# Sheet1.net
KiCad netlist of a schematic drawn in Altium Designer
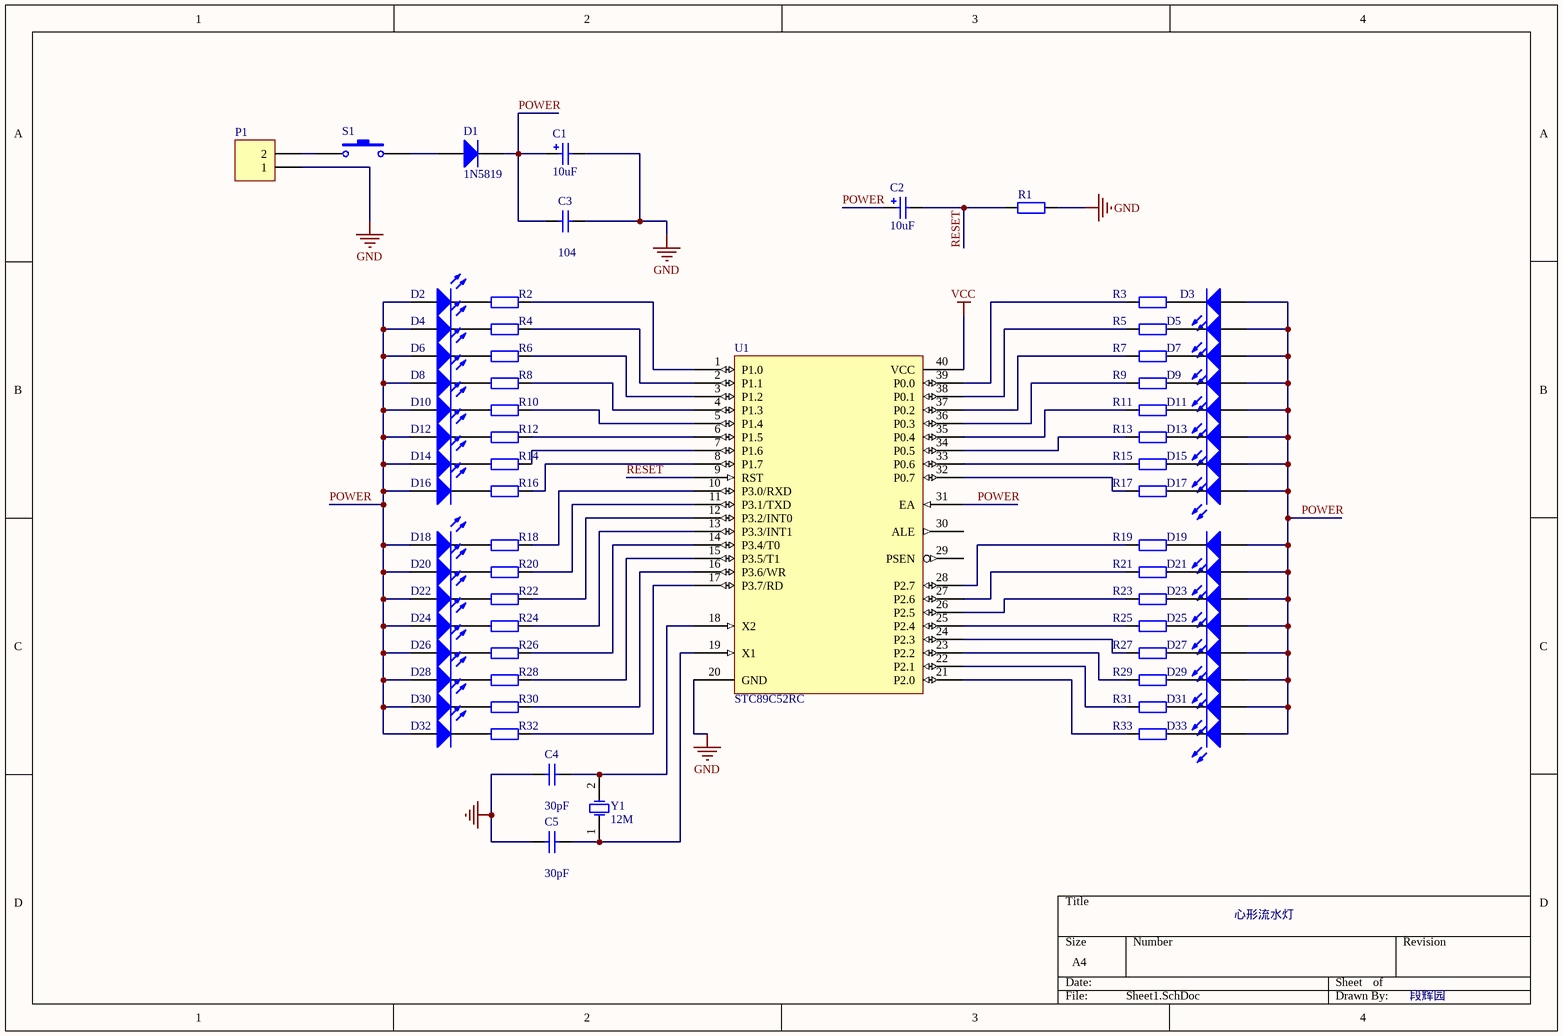
[diagram p0: Sheet1.SchDoc]

(export (version "E")
  (design (tool "Eeschema 10.0.6"))
  (components
    (comp (ref "C1")
      (value "10uF")
      (footprint "RB7.6-15")
      (description "Polarized Capacitor (Radial)")
      (fields (field (name "Comment") "Cap Pol1") (field (name "PUBLISHER") "Altium Limited"))
      (libsource (lib "Schlib1") (part "Cap Pol1"))
    )
    (comp (ref "C2")
      (value "10uF")
      (footprint "RB7.6-15")
      (description "Polarized Capacitor (Radial)")
      (fields (field (name "Comment") "Cap Pol1") (field (name "PUBLISHER") "Altium Limited"))
      (libsource (lib "Schlib1") (part "Cap Pol1"))
    )
    (comp (ref "C3")
      (value "104")
      (footprint "RAD-0.3")
      (description "Capacitor")
      (fields (field (name "Comment") "Cap") (field (name "PUBLISHER") "Altium Limited"))
      (libsource (lib "Miscellaneous Devices") (part "Cap"))
    )
    (comp (ref "C4")
      (value "30pF")
      (footprint "RAD-0.3")
      (description "Capacitor")
      (fields (field (name "Comment") "Cap") (field (name "PUBLISHER") "Altium Limited"))
      (libsource (lib "Schlib1") (part "Cap"))
    )
    (comp (ref "C5")
      (value "30pF")
      (footprint "RAD-0.3")
      (description "Capacitor")
      (fields (field (name "Comment") "Cap") (field (name "PUBLISHER") "Altium Limited"))
      (libsource (lib "Schlib1") (part "Cap"))
    )
    (comp (ref "D1")
      (value "1N5819")
      (footprint "DO-41")
      (description "1 Amp General Purpose Rectifier")
      (fields (field (name "PUBLISHER") "Altium Limited"))
      (libsource (lib "Schlib1") (part "Diode 1N4007"))
    )
    (comp (ref "D2")
      (value "LED0")
      (footprint "LED-0")
      (description "Typical INFRARED GaAs LED")
      (fields (field (name "PUBLISHER") "Altium Limited"))
      (libsource (lib "Schlib1") (part "LED0"))
    )
    (comp (ref "D3")
      (value "LED0")
      (footprint "LED-0")
      (description "Typical INFRARED GaAs LED")
      (fields (field (name "PUBLISHER") "Altium Limited"))
      (libsource (lib "Schlib1") (part "LED0"))
    )
    (comp (ref "D4")
      (value "LED0")
      (footprint "LED-0")
      (description "Typical INFRARED GaAs LED")
      (fields (field (name "PUBLISHER") "Altium Limited"))
      (libsource (lib "Schlib1") (part "LED0"))
    )
    (comp (ref "D5")
      (value "LED0")
      (footprint "LED-0")
      (description "Typical INFRARED GaAs LED")
      (fields (field (name "PUBLISHER") "Altium Limited"))
      (libsource (lib "Schlib1") (part "LED0"))
    )
    (comp (ref "D6")
      (value "LED0")
      (footprint "LED-0")
      (description "Typical INFRARED GaAs LED")
      (fields (field (name "PUBLISHER") "Altium Limited"))
      (libsource (lib "Schlib1") (part "LED0"))
    )
    (comp (ref "D7")
      (value "LED0")
      (footprint "LED-0")
      (description "Typical INFRARED GaAs LED")
      (fields (field (name "PUBLISHER") "Altium Limited"))
      (libsource (lib "Schlib1") (part "LED0"))
    )
    (comp (ref "D8")
      (value "LED0")
      (footprint "LED-0")
      (description "Typical INFRARED GaAs LED")
      (fields (field (name "PUBLISHER") "Altium Limited"))
      (libsource (lib "Schlib1") (part "LED0"))
    )
    (comp (ref "D9")
      (value "LED0")
      (footprint "LED-0")
      (description "Typical INFRARED GaAs LED")
      (fields (field (name "PUBLISHER") "Altium Limited"))
      (libsource (lib "Schlib1") (part "LED0"))
    )
    (comp (ref "D10")
      (value "LED0")
      (footprint "LED-0")
      (description "Typical INFRARED GaAs LED")
      (fields (field (name "PUBLISHER") "Altium Limited"))
      (libsource (lib "Schlib1") (part "LED0"))
    )
    (comp (ref "D11")
      (value "LED0")
      (footprint "LED-0")
      (description "Typical INFRARED GaAs LED")
      (fields (field (name "PUBLISHER") "Altium Limited"))
      (libsource (lib "Schlib1") (part "LED0"))
    )
    (comp (ref "D12")
      (value "LED0")
      (footprint "LED-0")
      (description "Typical INFRARED GaAs LED")
      (fields (field (name "PUBLISHER") "Altium Limited"))
      (libsource (lib "Schlib1") (part "LED0"))
    )
    (comp (ref "D13")
      (value "LED0")
      (footprint "LED-0")
      (description "Typical INFRARED GaAs LED")
      (fields (field (name "PUBLISHER") "Altium Limited"))
      (libsource (lib "Schlib1") (part "LED0"))
    )
    (comp (ref "D14")
      (value "LED0")
      (footprint "LED-0")
      (description "Typical INFRARED GaAs LED")
      (fields (field (name "PUBLISHER") "Altium Limited"))
      (libsource (lib "Schlib1") (part "LED0"))
    )
    (comp (ref "D15")
      (value "LED0")
      (footprint "LED-0")
      (description "Typical INFRARED GaAs LED")
      (fields (field (name "PUBLISHER") "Altium Limited"))
      (libsource (lib "Schlib1") (part "LED0"))
    )
    (comp (ref "D16")
      (value "LED0")
      (footprint "LED-0")
      (description "Typical INFRARED GaAs LED")
      (fields (field (name "PUBLISHER") "Altium Limited"))
      (libsource (lib "Schlib1") (part "LED0"))
    )
    (comp (ref "D17")
      (value "LED0")
      (footprint "LED-0")
      (description "Typical INFRARED GaAs LED")
      (fields (field (name "PUBLISHER") "Altium Limited"))
      (libsource (lib "Schlib1") (part "LED0"))
    )
    (comp (ref "D18")
      (value "LED0")
      (footprint "LED-0")
      (description "Typical INFRARED GaAs LED")
      (fields (field (name "PUBLISHER") "Altium Limited"))
      (libsource (lib "Schlib1") (part "LED0"))
    )
    (comp (ref "D19")
      (value "LED0")
      (footprint "LED-0")
      (description "Typical INFRARED GaAs LED")
      (fields (field (name "PUBLISHER") "Altium Limited"))
      (libsource (lib "Schlib1") (part "LED0"))
    )
    (comp (ref "D20")
      (value "LED0")
      (footprint "LED-0")
      (description "Typical INFRARED GaAs LED")
      (fields (field (name "PUBLISHER") "Altium Limited"))
      (libsource (lib "Schlib1") (part "LED0"))
    )
    (comp (ref "D21")
      (value "LED0")
      (footprint "LED-0")
      (description "Typical INFRARED GaAs LED")
      (fields (field (name "PUBLISHER") "Altium Limited"))
      (libsource (lib "Schlib1") (part "LED0"))
    )
    (comp (ref "D22")
      (value "LED0")
      (footprint "LED-0")
      (description "Typical INFRARED GaAs LED")
      (fields (field (name "PUBLISHER") "Altium Limited"))
      (libsource (lib "Schlib1") (part "LED0"))
    )
    (comp (ref "D23")
      (value "LED0")
      (footprint "LED-0")
      (description "Typical INFRARED GaAs LED")
      (fields (field (name "PUBLISHER") "Altium Limited"))
      (libsource (lib "Schlib1") (part "LED0"))
    )
    (comp (ref "D24")
      (value "LED0")
      (footprint "LED-0")
      (description "Typical INFRARED GaAs LED")
      (fields (field (name "PUBLISHER") "Altium Limited"))
      (libsource (lib "Schlib1") (part "LED0"))
    )
    (comp (ref "D25")
      (value "LED0")
      (footprint "LED-0")
      (description "Typical INFRARED GaAs LED")
      (fields (field (name "PUBLISHER") "Altium Limited"))
      (libsource (lib "Schlib1") (part "LED0"))
    )
    (comp (ref "D26")
      (value "LED0")
      (footprint "LED-0")
      (description "Typical INFRARED GaAs LED")
      (fields (field (name "PUBLISHER") "Altium Limited"))
      (libsource (lib "Schlib1") (part "LED0"))
    )
    (comp (ref "D27")
      (value "LED0")
      (footprint "LED-0")
      (description "Typical INFRARED GaAs LED")
      (fields (field (name "PUBLISHER") "Altium Limited"))
      (libsource (lib "Schlib1") (part "LED0"))
    )
    (comp (ref "D28")
      (value "LED0")
      (footprint "LED-0")
      (description "Typical INFRARED GaAs LED")
      (fields (field (name "PUBLISHER") "Altium Limited"))
      (libsource (lib "Schlib1") (part "LED0"))
    )
    (comp (ref "D29")
      (value "LED0")
      (footprint "LED-0")
      (description "Typical INFRARED GaAs LED")
      (fields (field (name "PUBLISHER") "Altium Limited"))
      (libsource (lib "Schlib1") (part "LED0"))
    )
    (comp (ref "D30")
      (value "LED0")
      (footprint "LED-0")
      (description "Typical INFRARED GaAs LED")
      (fields (field (name "PUBLISHER") "Altium Limited"))
      (libsource (lib "Schlib1") (part "LED0"))
    )
    (comp (ref "D31")
      (value "LED0")
      (footprint "LED-0")
      (description "Typical INFRARED GaAs LED")
      (fields (field (name "PUBLISHER") "Altium Limited"))
      (libsource (lib "Schlib1") (part "LED0"))
    )
    (comp (ref "D32")
      (value "LED0")
      (footprint "LED-0")
      (description "Typical INFRARED GaAs LED")
      (fields (field (name "PUBLISHER") "Altium Limited"))
      (libsource (lib "Schlib1") (part "LED0"))
    )
    (comp (ref "D33")
      (value "LED0")
      (footprint "LED-0")
      (description "Typical INFRARED GaAs LED")
      (fields (field (name "PUBLISHER") "Altium Limited"))
      (libsource (lib "Schlib1") (part "LED0"))
    )
    (comp (ref "P1")
      (value "Header 2")
      (footprint "HDR1X2")
      (description "Header, 2-Pin")
      (fields (field (name "PUBLISHER") "Altium Limited"))
      (libsource (lib "Miscellaneous Connectors") (part "Header 2"))
    )
    (comp (ref "R1")
      (value "Res2")
      (footprint "AXIAL-0.4")
      (description "Resistor")
      (fields (field (name "PUBLISHER") "Altium Limited"))
      (libsource (lib "Schlib1") (part "Res2"))
    )
    (comp (ref "R2")
      (value "Res2")
      (footprint "AXIAL-0.4")
      (description "Resistor")
      (fields (field (name "PUBLISHER") "Altium Limited"))
      (libsource (lib "Schlib1") (part "Res2"))
    )
    (comp (ref "R3")
      (value "Res2")
      (footprint "AXIAL-0.4")
      (description "Resistor")
      (fields (field (name "PUBLISHER") "Altium Limited"))
      (libsource (lib "Schlib1") (part "Res2"))
    )
    (comp (ref "R4")
      (value "Res2")
      (footprint "AXIAL-0.4")
      (description "Resistor")
      (fields (field (name "PUBLISHER") "Altium Limited"))
      (libsource (lib "Schlib1") (part "Res2"))
    )
    (comp (ref "R5")
      (value "Res2")
      (footprint "AXIAL-0.4")
      (description "Resistor")
      (fields (field (name "PUBLISHER") "Altium Limited"))
      (libsource (lib "Schlib1") (part "Res2"))
    )
    (comp (ref "R6")
      (value "Res2")
      (footprint "AXIAL-0.4")
      (description "Resistor")
      (fields (field (name "PUBLISHER") "Altium Limited"))
      (libsource (lib "Schlib1") (part "Res2"))
    )
    (comp (ref "R7")
      (value "Res2")
      (footprint "AXIAL-0.4")
      (description "Resistor")
      (fields (field (name "PUBLISHER") "Altium Limited"))
      (libsource (lib "Schlib1") (part "Res2"))
    )
    (comp (ref "R8")
      (value "Res2")
      (footprint "AXIAL-0.4")
      (description "Resistor")
      (fields (field (name "PUBLISHER") "Altium Limited"))
      (libsource (lib "Schlib1") (part "Res2"))
    )
    (comp (ref "R9")
      (value "Res2")
      (footprint "AXIAL-0.4")
      (description "Resistor")
      (fields (field (name "PUBLISHER") "Altium Limited"))
      (libsource (lib "Schlib1") (part "Res2"))
    )
    (comp (ref "R10")
      (value "Res2")
      (footprint "AXIAL-0.4")
      (description "Resistor")
      (fields (field (name "PUBLISHER") "Altium Limited"))
      (libsource (lib "Schlib1") (part "Res2"))
    )
    (comp (ref "R11")
      (value "Res2")
      (footprint "AXIAL-0.4")
      (description "Resistor")
      (fields (field (name "PUBLISHER") "Altium Limited"))
      (libsource (lib "Schlib1") (part "Res2"))
    )
    (comp (ref "R12")
      (value "Res2")
      (footprint "AXIAL-0.4")
      (description "Resistor")
      (fields (field (name "PUBLISHER") "Altium Limited"))
      (libsource (lib "Schlib1") (part "Res2"))
    )
    (comp (ref "R13")
      (value "Res2")
      (footprint "AXIAL-0.4")
      (description "Resistor")
      (fields (field (name "PUBLISHER") "Altium Limited"))
      (libsource (lib "Schlib1") (part "Res2"))
    )
    (comp (ref "R14")
      (value "Res2")
      (footprint "AXIAL-0.4")
      (description "Resistor")
      (fields (field (name "PUBLISHER") "Altium Limited"))
      (libsource (lib "Schlib1") (part "Res2"))
    )
    (comp (ref "R15")
      (value "Res2")
      (footprint "AXIAL-0.4")
      (description "Resistor")
      (fields (field (name "PUBLISHER") "Altium Limited"))
      (libsource (lib "Schlib1") (part "Res2"))
    )
    (comp (ref "R16")
      (value "Res2")
      (footprint "AXIAL-0.4")
      (description "Resistor")
      (fields (field (name "PUBLISHER") "Altium Limited"))
      (libsource (lib "Schlib1") (part "Res2"))
    )
    (comp (ref "R17")
      (value "Res2")
      (footprint "AXIAL-0.4")
      (description "Resistor")
      (fields (field (name "PUBLISHER") "Altium Limited"))
      (libsource (lib "Schlib1") (part "Res2"))
    )
    (comp (ref "R18")
      (value "Res2")
      (footprint "AXIAL-0.4")
      (description "Resistor")
      (fields (field (name "PUBLISHER") "Altium Limited"))
      (libsource (lib "Schlib1") (part "Res2"))
    )
    (comp (ref "R19")
      (value "Res2")
      (footprint "AXIAL-0.4")
      (description "Resistor")
      (fields (field (name "PUBLISHER") "Altium Limited"))
      (libsource (lib "Schlib1") (part "Res2"))
    )
    (comp (ref "R20")
      (value "Res2")
      (footprint "AXIAL-0.4")
      (description "Resistor")
      (fields (field (name "PUBLISHER") "Altium Limited"))
      (libsource (lib "Schlib1") (part "Res2"))
    )
    (comp (ref "R21")
      (value "Res2")
      (footprint "AXIAL-0.4")
      (description "Resistor")
      (fields (field (name "PUBLISHER") "Altium Limited"))
      (libsource (lib "Schlib1") (part "Res2"))
    )
    (comp (ref "R22")
      (value "Res2")
      (footprint "AXIAL-0.4")
      (description "Resistor")
      (fields (field (name "PUBLISHER") "Altium Limited"))
      (libsource (lib "Schlib1") (part "Res2"))
    )
    (comp (ref "R23")
      (value "Res2")
      (footprint "AXIAL-0.4")
      (description "Resistor")
      (fields (field (name "PUBLISHER") "Altium Limited"))
      (libsource (lib "Schlib1") (part "Res2"))
    )
    (comp (ref "R24")
      (value "Res2")
      (footprint "AXIAL-0.4")
      (description "Resistor")
      (fields (field (name "PUBLISHER") "Altium Limited"))
      (libsource (lib "Schlib1") (part "Res2"))
    )
    (comp (ref "R25")
      (value "Res2")
      (footprint "AXIAL-0.4")
      (description "Resistor")
      (fields (field (name "PUBLISHER") "Altium Limited"))
      (libsource (lib "Schlib1") (part "Res2"))
    )
    (comp (ref "R26")
      (value "Res2")
      (footprint "AXIAL-0.4")
      (description "Resistor")
      (fields (field (name "PUBLISHER") "Altium Limited"))
      (libsource (lib "Schlib1") (part "Res2"))
    )
    (comp (ref "R27")
      (value "Res2")
      (footprint "AXIAL-0.4")
      (description "Resistor")
      (fields (field (name "PUBLISHER") "Altium Limited"))
      (libsource (lib "Schlib1") (part "Res2"))
    )
    (comp (ref "R28")
      (value "Res2")
      (footprint "AXIAL-0.4")
      (description "Resistor")
      (fields (field (name "PUBLISHER") "Altium Limited"))
      (libsource (lib "Schlib1") (part "Res2"))
    )
    (comp (ref "R29")
      (value "Res2")
      (footprint "AXIAL-0.4")
      (description "Resistor")
      (fields (field (name "PUBLISHER") "Altium Limited"))
      (libsource (lib "Schlib1") (part "Res2"))
    )
    (comp (ref "R30")
      (value "Res2")
      (footprint "AXIAL-0.4")
      (description "Resistor")
      (fields (field (name "PUBLISHER") "Altium Limited"))
      (libsource (lib "Schlib1") (part "Res2"))
    )
    (comp (ref "R31")
      (value "Res2")
      (footprint "AXIAL-0.4")
      (description "Resistor")
      (fields (field (name "PUBLISHER") "Altium Limited"))
      (libsource (lib "Schlib1") (part "Res2"))
    )
    (comp (ref "R32")
      (value "Res2")
      (footprint "AXIAL-0.4")
      (description "Resistor")
      (fields (field (name "PUBLISHER") "Altium Limited"))
      (libsource (lib "Schlib1") (part "Res2"))
    )
    (comp (ref "R33")
      (value "Res2")
      (footprint "AXIAL-0.4")
      (description "Resistor")
      (fields (field (name "PUBLISHER") "Altium Limited"))
      (libsource (lib "Schlib1") (part "Res2"))
    )
    (comp (ref "S1")
      (value "SW-PB")
      (footprint "SPST-2")
      (description "Switch")
      (fields (field (name "PUBLISHER") "Altium Limited"))
      (libsource (lib "Miscellaneous Devices") (part "SW-PB"))
    )
    (comp (ref "U1")
      (value "STC89C52RC")
      (footprint "DIP40 - duplicate")
      (libsource (lib "Schlib1") (part "STC89C52RC"))
    )
    (comp (ref "Y1")
      (value "12M")
      (footprint "R38")
      (description "Crystal Oscillator")
      (fields (field (name "PUBLISHER") "Altium Limited"))
      (libsource (lib "Schlib1") (part "XTAL"))
    )
  )
  (nets
    (net (code "1") (name "/POWER") (class "Default")
      (node (ref "C1") (pin "1") (pinfunction "1_1") (pintype "passive"))
      (node (ref "C2") (pin "1") (pinfunction "1_1") (pintype "passive"))
      (node (ref "C3") (pin "1") (pinfunction "1_1") (pintype "passive"))
      (node (ref "D1") (pin "2") (pinfunction "K_2") (pintype "passive"))
      (node (ref "D10") (pin "1") (pinfunction "A_1") (pintype "passive"))
      (node (ref "D11") (pin "1") (pinfunction "A_1") (pintype "passive"))
      (node (ref "D12") (pin "1") (pinfunction "A_1") (pintype "passive"))
      (node (ref "D13") (pin "1") (pinfunction "A_1") (pintype "passive"))
      (node (ref "D14") (pin "1") (pinfunction "A_1") (pintype "passive"))
      (node (ref "D15") (pin "1") (pinfunction "A_1") (pintype "passive"))
      (node (ref "D16") (pin "1") (pinfunction "A_1") (pintype "passive"))
      (node (ref "D17") (pin "1") (pinfunction "A_1") (pintype "passive"))
      (node (ref "D18") (pin "1") (pinfunction "A_1") (pintype "passive"))
      (node (ref "D19") (pin "1") (pinfunction "A_1") (pintype "passive"))
      (node (ref "D2") (pin "1") (pinfunction "A_1") (pintype "passive"))
      (node (ref "D20") (pin "1") (pinfunction "A_1") (pintype "passive"))
      (node (ref "D21") (pin "1") (pinfunction "A_1") (pintype "passive"))
      (node (ref "D22") (pin "1") (pinfunction "A_1") (pintype "passive"))
      (node (ref "D23") (pin "1") (pinfunction "A_1") (pintype "passive"))
      (node (ref "D24") (pin "1") (pinfunction "A_1") (pintype "passive"))
      (node (ref "D25") (pin "1") (pinfunction "A_1") (pintype "passive"))
      (node (ref "D26") (pin "1") (pinfunction "A_1") (pintype "passive"))
      (node (ref "D27") (pin "1") (pinfunction "A_1") (pintype "passive"))
      (node (ref "D28") (pin "1") (pinfunction "A_1") (pintype "passive"))
      (node (ref "D29") (pin "1") (pinfunction "A_1") (pintype "passive"))
      (node (ref "D3") (pin "1") (pinfunction "A_1") (pintype "passive"))
      (node (ref "D30") (pin "1") (pinfunction "A_1") (pintype "passive"))
      (node (ref "D31") (pin "1") (pinfunction "A_1") (pintype "passive"))
      (node (ref "D32") (pin "1") (pinfunction "A_1") (pintype "passive"))
      (node (ref "D33") (pin "1") (pinfunction "A_1") (pintype "passive"))
      (node (ref "D4") (pin "1") (pinfunction "A_1") (pintype "passive"))
      (node (ref "D5") (pin "1") (pinfunction "A_1") (pintype "passive"))
      (node (ref "D6") (pin "1") (pinfunction "A_1") (pintype "passive"))
      (node (ref "D7") (pin "1") (pinfunction "A_1") (pintype "passive"))
      (node (ref "D8") (pin "1") (pinfunction "A_1") (pintype "passive"))
      (node (ref "D9") (pin "1") (pinfunction "A_1") (pintype "passive"))
      (node (ref "U1") (pin "31") (pinfunction "EA_31") (pintype "input"))
    )
    (net (code "2") (name "/RESET") (class "Default")
      (node (ref "C2") (pin "2") (pinfunction "2_2") (pintype "passive"))
      (node (ref "R1") (pin "1") (pinfunction "1_1") (pintype "passive"))
      (node (ref "U1") (pin "9") (pinfunction "RST_9") (pintype "input"))
    )
    (net (code "3") (name "GND") (class "Default")
      (node (ref "C1") (pin "2") (pinfunction "2_2") (pintype "passive"))
      (node (ref "C3") (pin "2") (pinfunction "2_2") (pintype "passive"))
      (node (ref "C4") (pin "1") (pinfunction "1_1") (pintype "passive"))
      (node (ref "C5") (pin "1") (pinfunction "1_1") (pintype "passive"))
      (node (ref "P1") (pin "1") (pinfunction "1_1") (pintype "passive"))
      (node (ref "R1") (pin "2") (pinfunction "2_2") (pintype "passive"))
      (node (ref "U1") (pin "20") (pinfunction "GND_20") (pintype "power_in"))
    )
    (net (code "4") (name "Net-(D1-A)") (class "Default")
      (node (ref "D1") (pin "1") (pinfunction "A_1") (pintype "passive"))
      (node (ref "S1") (pin "2") (pinfunction "2_2") (pintype "passive"))
    )
    (net (code "5") (name "Net-(D2-K)") (class "Default")
      (node (ref "D2") (pin "2") (pinfunction "K_2") (pintype "passive"))
      (node (ref "R2") (pin "1") (pinfunction "1_1") (pintype "passive"))
    )
    (net (code "6") (name "Net-(D3-K)") (class "Default")
      (node (ref "D3") (pin "2") (pinfunction "K_2") (pintype "passive"))
      (node (ref "R3") (pin "2") (pinfunction "2_2") (pintype "passive"))
    )
    (net (code "7") (name "Net-(D4-K)") (class "Default")
      (node (ref "D4") (pin "2") (pinfunction "K_2") (pintype "passive"))
      (node (ref "R4") (pin "1") (pinfunction "1_1") (pintype "passive"))
    )
    (net (code "8") (name "Net-(D5-K)") (class "Default")
      (node (ref "D5") (pin "2") (pinfunction "K_2") (pintype "passive"))
      (node (ref "R5") (pin "2") (pinfunction "2_2") (pintype "passive"))
    )
    (net (code "9") (name "Net-(D6-K)") (class "Default")
      (node (ref "D6") (pin "2") (pinfunction "K_2") (pintype "passive"))
      (node (ref "R6") (pin "1") (pinfunction "1_1") (pintype "passive"))
    )
    (net (code "10") (name "Net-(D7-K)") (class "Default")
      (node (ref "D7") (pin "2") (pinfunction "K_2") (pintype "passive"))
      (node (ref "R7") (pin "2") (pinfunction "2_2") (pintype "passive"))
    )
    (net (code "11") (name "Net-(D8-K)") (class "Default")
      (node (ref "D8") (pin "2") (pinfunction "K_2") (pintype "passive"))
      (node (ref "R8") (pin "1") (pinfunction "1_1") (pintype "passive"))
    )
    (net (code "12") (name "Net-(D9-K)") (class "Default")
      (node (ref "D9") (pin "2") (pinfunction "K_2") (pintype "passive"))
      (node (ref "R9") (pin "2") (pinfunction "2_2") (pintype "passive"))
    )
    (net (code "13") (name "Net-(D10-K)") (class "Default")
      (node (ref "D10") (pin "2") (pinfunction "K_2") (pintype "passive"))
      (node (ref "R10") (pin "1") (pinfunction "1_1") (pintype "passive"))
    )
    (net (code "14") (name "Net-(D11-K)") (class "Default")
      (node (ref "D11") (pin "2") (pinfunction "K_2") (pintype "passive"))
      (node (ref "R11") (pin "2") (pinfunction "2_2") (pintype "passive"))
    )
    (net (code "15") (name "Net-(D12-K)") (class "Default")
      (node (ref "D12") (pin "2") (pinfunction "K_2") (pintype "passive"))
      (node (ref "R12") (pin "1") (pinfunction "1_1") (pintype "passive"))
    )
    (net (code "16") (name "Net-(D13-K)") (class "Default")
      (node (ref "D13") (pin "2") (pinfunction "K_2") (pintype "passive"))
      (node (ref "R13") (pin "2") (pinfunction "2_2") (pintype "passive"))
    )
    (net (code "17") (name "Net-(D14-K)") (class "Default")
      (node (ref "D14") (pin "2") (pinfunction "K_2") (pintype "passive"))
      (node (ref "R14") (pin "1") (pinfunction "1_1") (pintype "passive"))
    )
    (net (code "18") (name "Net-(D15-K)") (class "Default")
      (node (ref "D15") (pin "2") (pinfunction "K_2") (pintype "passive"))
      (node (ref "R15") (pin "2") (pinfunction "2_2") (pintype "passive"))
    )
    (net (code "19") (name "Net-(D16-K)") (class "Default")
      (node (ref "D16") (pin "2") (pinfunction "K_2") (pintype "passive"))
      (node (ref "R16") (pin "1") (pinfunction "1_1") (pintype "passive"))
    )
    (net (code "20") (name "Net-(D17-K)") (class "Default")
      (node (ref "D17") (pin "2") (pinfunction "K_2") (pintype "passive"))
      (node (ref "R17") (pin "2") (pinfunction "2_2") (pintype "passive"))
    )
    (net (code "21") (name "Net-(D18-K)") (class "Default")
      (node (ref "D18") (pin "2") (pinfunction "K_2") (pintype "passive"))
      (node (ref "R18") (pin "1") (pinfunction "1_1") (pintype "passive"))
    )
    (net (code "22") (name "Net-(D19-K)") (class "Default")
      (node (ref "D19") (pin "2") (pinfunction "K_2") (pintype "passive"))
      (node (ref "R19") (pin "2") (pinfunction "2_2") (pintype "passive"))
    )
    (net (code "23") (name "Net-(D20-K)") (class "Default")
      (node (ref "D20") (pin "2") (pinfunction "K_2") (pintype "passive"))
      (node (ref "R20") (pin "1") (pinfunction "1_1") (pintype "passive"))
    )
    (net (code "24") (name "Net-(D21-K)") (class "Default")
      (node (ref "D21") (pin "2") (pinfunction "K_2") (pintype "passive"))
      (node (ref "R21") (pin "2") (pinfunction "2_2") (pintype "passive"))
    )
    (net (code "25") (name "Net-(D22-K)") (class "Default")
      (node (ref "D22") (pin "2") (pinfunction "K_2") (pintype "passive"))
      (node (ref "R22") (pin "1") (pinfunction "1_1") (pintype "passive"))
    )
    (net (code "26") (name "Net-(D23-K)") (class "Default")
      (node (ref "D23") (pin "2") (pinfunction "K_2") (pintype "passive"))
      (node (ref "R23") (pin "2") (pinfunction "2_2") (pintype "passive"))
    )
    (net (code "27") (name "Net-(D24-K)") (class "Default")
      (node (ref "D24") (pin "2") (pinfunction "K_2") (pintype "passive"))
      (node (ref "R24") (pin "1") (pinfunction "1_1") (pintype "passive"))
    )
    (net (code "28") (name "Net-(D25-K)") (class "Default")
      (node (ref "D25") (pin "2") (pinfunction "K_2") (pintype "passive"))
      (node (ref "R25") (pin "2") (pinfunction "2_2") (pintype "passive"))
    )
    (net (code "29") (name "Net-(D26-K)") (class "Default")
      (node (ref "D26") (pin "2") (pinfunction "K_2") (pintype "passive"))
      (node (ref "R26") (pin "1") (pinfunction "1_1") (pintype "passive"))
    )
    (net (code "30") (name "Net-(D27-K)") (class "Default")
      (node (ref "D27") (pin "2") (pinfunction "K_2") (pintype "passive"))
      (node (ref "R27") (pin "2") (pinfunction "2_2") (pintype "passive"))
    )
    (net (code "31") (name "Net-(D28-K)") (class "Default")
      (node (ref "D28") (pin "2") (pinfunction "K_2") (pintype "passive"))
      (node (ref "R28") (pin "1") (pinfunction "1_1") (pintype "passive"))
    )
    (net (code "32") (name "Net-(D29-K)") (class "Default")
      (node (ref "D29") (pin "2") (pinfunction "K_2") (pintype "passive"))
      (node (ref "R29") (pin "2") (pinfunction "2_2") (pintype "passive"))
    )
    (net (code "33") (name "Net-(D30-K)") (class "Default")
      (node (ref "D30") (pin "2") (pinfunction "K_2") (pintype "passive"))
      (node (ref "R30") (pin "1") (pinfunction "1_1") (pintype "passive"))
    )
    (net (code "34") (name "Net-(D31-K)") (class "Default")
      (node (ref "D31") (pin "2") (pinfunction "K_2") (pintype "passive"))
      (node (ref "R31") (pin "2") (pinfunction "2_2") (pintype "passive"))
    )
    (net (code "35") (name "Net-(D32-K)") (class "Default")
      (node (ref "D32") (pin "2") (pinfunction "K_2") (pintype "passive"))
      (node (ref "R32") (pin "1") (pinfunction "1_1") (pintype "passive"))
    )
    (net (code "36") (name "Net-(D33-K)") (class "Default")
      (node (ref "D33") (pin "2") (pinfunction "K_2") (pintype "passive"))
      (node (ref "R33") (pin "2") (pinfunction "2_2") (pintype "passive"))
    )
    (net (code "37") (name "Net-(P1-Pad2)") (class "Default")
      (node (ref "P1") (pin "2") (pinfunction "2_2") (pintype "passive"))
      (node (ref "S1") (pin "1") (pinfunction "1_1") (pintype "passive"))
    )
    (net (code "38") (name "Net-(U1-P0.0)") (class "Default")
      (node (ref "R3") (pin "1") (pinfunction "1_1") (pintype "passive"))
      (node (ref "U1") (pin "39") (pinfunction "P0.0_39") (pintype "bidirectional"))
    )
    (net (code "39") (name "Net-(U1-P0.1)") (class "Default")
      (node (ref "R5") (pin "1") (pinfunction "1_1") (pintype "passive"))
      (node (ref "U1") (pin "38") (pinfunction "P0.1_38") (pintype "bidirectional"))
    )
    (net (code "40") (name "Net-(U1-P0.2)") (class "Default")
      (node (ref "R7") (pin "1") (pinfunction "1_1") (pintype "passive"))
      (node (ref "U1") (pin "37") (pinfunction "P0.2_37") (pintype "bidirectional"))
    )
    (net (code "41") (name "Net-(U1-P0.3)") (class "Default")
      (node (ref "R9") (pin "1") (pinfunction "1_1") (pintype "passive"))
      (node (ref "U1") (pin "36") (pinfunction "P0.3_36") (pintype "bidirectional"))
    )
    (net (code "42") (name "Net-(U1-P0.4)") (class "Default")
      (node (ref "R11") (pin "1") (pinfunction "1_1") (pintype "passive"))
      (node (ref "U1") (pin "35") (pinfunction "P0.4_35") (pintype "bidirectional"))
    )
    (net (code "43") (name "Net-(U1-P0.5)") (class "Default")
      (node (ref "R13") (pin "1") (pinfunction "1_1") (pintype "passive"))
      (node (ref "U1") (pin "34") (pinfunction "P0.5_34") (pintype "bidirectional"))
    )
    (net (code "44") (name "Net-(U1-P0.6)") (class "Default")
      (node (ref "R15") (pin "1") (pinfunction "1_1") (pintype "passive"))
      (node (ref "U1") (pin "33") (pinfunction "P0.6_33") (pintype "bidirectional"))
    )
    (net (code "45") (name "Net-(U1-P0.7)") (class "Default")
      (node (ref "R17") (pin "1") (pinfunction "1_1") (pintype "passive"))
      (node (ref "U1") (pin "32") (pinfunction "P0.7_32") (pintype "bidirectional"))
    )
    (net (code "46") (name "Net-(U1-P1.0)") (class "Default")
      (node (ref "R2") (pin "2") (pinfunction "2_2") (pintype "passive"))
      (node (ref "U1") (pin "1") (pinfunction "P1.0_1") (pintype "bidirectional"))
    )
    (net (code "47") (name "Net-(U1-P1.1)") (class "Default")
      (node (ref "R4") (pin "2") (pinfunction "2_2") (pintype "passive"))
      (node (ref "U1") (pin "2") (pinfunction "P1.1_2") (pintype "bidirectional"))
    )
    (net (code "48") (name "Net-(U1-P1.2)") (class "Default")
      (node (ref "R6") (pin "2") (pinfunction "2_2") (pintype "passive"))
      (node (ref "U1") (pin "3") (pinfunction "P1.2_3") (pintype "bidirectional"))
    )
    (net (code "49") (name "Net-(U1-P1.3)") (class "Default")
      (node (ref "R8") (pin "2") (pinfunction "2_2") (pintype "passive"))
      (node (ref "U1") (pin "4") (pinfunction "P1.3_4") (pintype "bidirectional"))
    )
    (net (code "50") (name "Net-(U1-P1.4)") (class "Default")
      (node (ref "R10") (pin "2") (pinfunction "2_2") (pintype "passive"))
      (node (ref "U1") (pin "5") (pinfunction "P1.4_5") (pintype "bidirectional"))
    )
    (net (code "51") (name "Net-(U1-P1.5)") (class "Default")
      (node (ref "R12") (pin "2") (pinfunction "2_2") (pintype "passive"))
      (node (ref "U1") (pin "6") (pinfunction "P1.5_6") (pintype "bidirectional"))
    )
    (net (code "52") (name "Net-(U1-P1.6)") (class "Default")
      (node (ref "R14") (pin "2") (pinfunction "2_2") (pintype "passive"))
      (node (ref "U1") (pin "7") (pinfunction "P1.6_7") (pintype "bidirectional"))
    )
    (net (code "53") (name "Net-(U1-P1.7)") (class "Default")
      (node (ref "R16") (pin "2") (pinfunction "2_2") (pintype "passive"))
      (node (ref "U1") (pin "8") (pinfunction "P1.7_8") (pintype "bidirectional"))
    )
    (net (code "54") (name "Net-(U1-P2.0)") (class "Default")
      (node (ref "R33") (pin "1") (pinfunction "1_1") (pintype "passive"))
      (node (ref "U1") (pin "21") (pinfunction "P2.0_21") (pintype "bidirectional"))
    )
    (net (code "55") (name "Net-(U1-P2.1)") (class "Default")
      (node (ref "R31") (pin "1") (pinfunction "1_1") (pintype "passive"))
      (node (ref "U1") (pin "22") (pinfunction "P2.1_22") (pintype "bidirectional"))
    )
    (net (code "56") (name "Net-(U1-P2.2)") (class "Default")
      (node (ref "R29") (pin "1") (pinfunction "1_1") (pintype "passive"))
      (node (ref "U1") (pin "23") (pinfunction "P2.2_23") (pintype "bidirectional"))
    )
    (net (code "57") (name "Net-(U1-P2.3)") (class "Default")
      (node (ref "R27") (pin "1") (pinfunction "1_1") (pintype "passive"))
      (node (ref "U1") (pin "24") (pinfunction "P2.3_24") (pintype "bidirectional"))
    )
    (net (code "58") (name "Net-(U1-P2.4)") (class "Default")
      (node (ref "R25") (pin "1") (pinfunction "1_1") (pintype "passive"))
      (node (ref "U1") (pin "25") (pinfunction "P2.4_25") (pintype "bidirectional"))
    )
    (net (code "59") (name "Net-(U1-P2.5)") (class "Default")
      (node (ref "R23") (pin "1") (pinfunction "1_1") (pintype "passive"))
      (node (ref "U1") (pin "26") (pinfunction "P2.5_26") (pintype "bidirectional"))
    )
    (net (code "60") (name "Net-(U1-P2.6)") (class "Default")
      (node (ref "R21") (pin "1") (pinfunction "1_1") (pintype "passive"))
      (node (ref "U1") (pin "27") (pinfunction "P2.6_27") (pintype "bidirectional"))
    )
    (net (code "61") (name "Net-(U1-P2.7)") (class "Default")
      (node (ref "R19") (pin "1") (pinfunction "1_1") (pintype "passive"))
      (node (ref "U1") (pin "28") (pinfunction "P2.7_28") (pintype "bidirectional"))
    )
    (net (code "62") (name "Net-(U1-P3.0{slash}RXD)") (class "Default")
      (node (ref "R18") (pin "2") (pinfunction "2_2") (pintype "passive"))
      (node (ref "U1") (pin "10") (pinfunction "P3.0/RXD_10") (pintype "bidirectional"))
    )
    (net (code "63") (name "Net-(U1-P3.1{slash}TXD)") (class "Default")
      (node (ref "R20") (pin "2") (pinfunction "2_2") (pintype "passive"))
      (node (ref "U1") (pin "11") (pinfunction "P3.1/TXD_11") (pintype "bidirectional"))
    )
    (net (code "64") (name "Net-(U1-P3.2{slash}INT0)") (class "Default")
      (node (ref "R22") (pin "2") (pinfunction "2_2") (pintype "passive"))
      (node (ref "U1") (pin "12") (pinfunction "P3.2/INT0_12") (pintype "bidirectional"))
    )
    (net (code "65") (name "Net-(U1-P3.3{slash}INT1)") (class "Default")
      (node (ref "R24") (pin "2") (pinfunction "2_2") (pintype "passive"))
      (node (ref "U1") (pin "13") (pinfunction "P3.3/INT1_13") (pintype "bidirectional"))
    )
    (net (code "66") (name "Net-(U1-P3.4{slash}T0)") (class "Default")
      (node (ref "R26") (pin "2") (pinfunction "2_2") (pintype "passive"))
      (node (ref "U1") (pin "14") (pinfunction "P3.4/T0_14") (pintype "bidirectional"))
    )
    (net (code "67") (name "Net-(U1-P3.5{slash}T1)") (class "Default")
      (node (ref "R28") (pin "2") (pinfunction "2_2") (pintype "passive"))
      (node (ref "U1") (pin "15") (pinfunction "P3.5/T1_15") (pintype "bidirectional"))
    )
    (net (code "68") (name "Net-(U1-P3.6{slash}WR)") (class "Default")
      (node (ref "R30") (pin "2") (pinfunction "2_2") (pintype "passive"))
      (node (ref "U1") (pin "16") (pinfunction "P3.6/WR_16") (pintype "bidirectional"))
    )
    (net (code "69") (name "Net-(U1-P3.7{slash}RD)") (class "Default")
      (node (ref "R32") (pin "2") (pinfunction "2_2") (pintype "passive"))
      (node (ref "U1") (pin "17") (pinfunction "P3.7/RD_17") (pintype "bidirectional"))
    )
    (net (code "70") (name "Net-(U1-X1)") (class "Default")
      (node (ref "C5") (pin "2") (pinfunction "2_2") (pintype "passive"))
      (node (ref "U1") (pin "19") (pinfunction "X1_19") (pintype "input"))
      (node (ref "Y1") (pin "1") (pinfunction "OSC1_1") (pintype "passive"))
    )
    (net (code "71") (name "Net-(U1-X2)") (class "Default")
      (node (ref "C4") (pin "2") (pinfunction "2_2") (pintype "passive"))
      (node (ref "U1") (pin "18") (pinfunction "X2_18") (pintype "input"))
      (node (ref "Y1") (pin "2") (pinfunction "OSC2_2") (pintype "passive"))
    )
    (net (code "72") (name "VCC") (class "Default")
      (node (ref "U1") (pin "40") (pinfunction "VCC_40") (pintype "power_in"))
    )
    (net (code "73") (name "unconnected-(U1-ALE-Pad30)") (class "Default")
      (node (ref "U1") (pin "30") (pinfunction "ALE_30") (pintype "output"))
    )
    (net (code "74") (name "unconnected-(U1-PSEN-Pad29)") (class "Default")
      (node (ref "U1") (pin "29") (pinfunction "PSEN_29") (pintype "output"))
    )
  )
)
